# PMP20634_Sheet1.net
KiCad netlist of a schematic drawn in Altium Designer
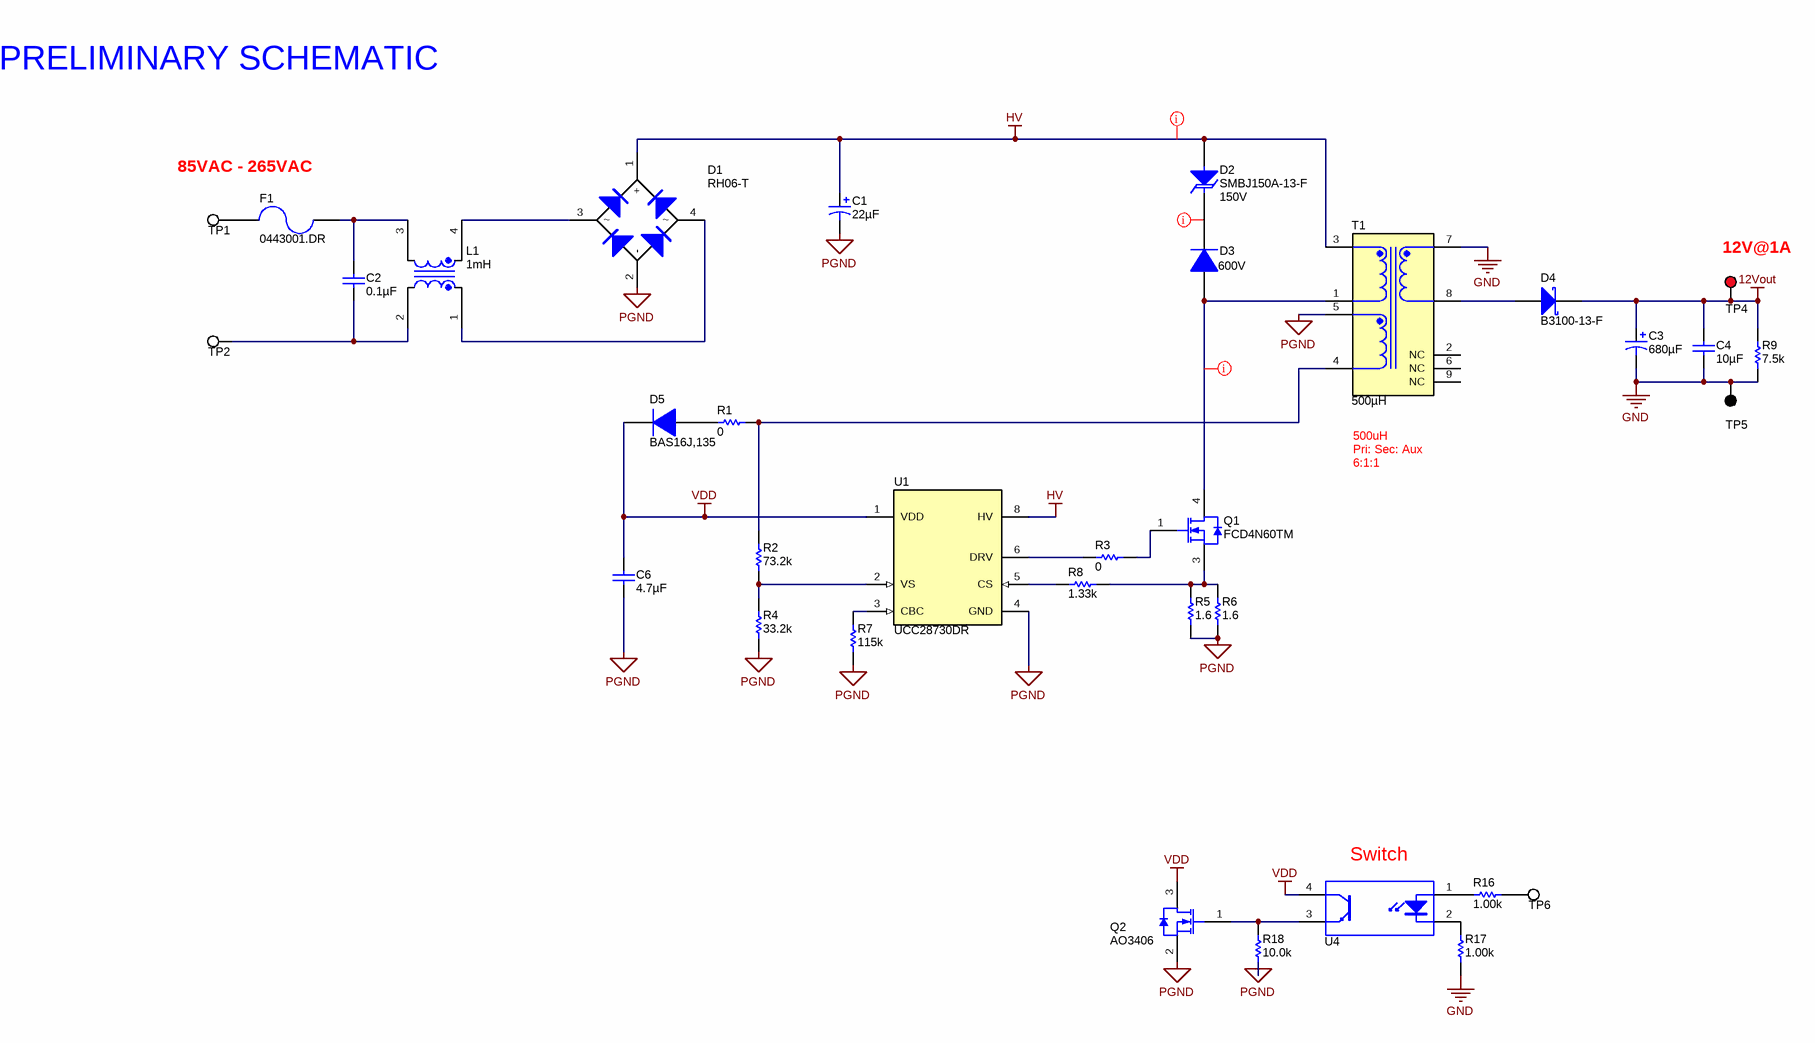
[diagram p0: PMP20634_Sheet1.SchDoc]

(export (version "E")
  (design (tool "Eeschema 10.0.6"))
  (components
    (comp (ref "C1")
      (value "EKXG401ELL220MK20S")
      (footprint "KXG_1250x2000")
      (description "CAP, AL, 22 µF, 400 V, +/- 20%, TH")
      (fields
        (field (name "VALUEDISPLAYED") "22µF")
        (field (name "MANUFACTURER") "Chemi-Con")
        (field (name "PUBLISHER") "Texas Instruments")
      )
      (libsource (lib "Capacitor_Aluminum") (part "EKXG401ELL220MK20S"))
    )
    (comp (ref "C2")
      (value "ECQ-U3A104MG")
      (footprint "ECQUG_1500x800x1500")
      (description "CAP, Film, 0.1 µF, 300 V, +/- 20%, TH")
      (fields
        (field (name "VALUEDISPLAYED") "0.1µF")
        (field (name "MANUFACTURER") "Panasonic")
        (field (name "PUBLISHER") "Texas Instruments")
      )
      (libsource (lib "Capacitor_Other") (part "ECQ-U3A104MG"))
    )
    (comp (ref "C3")
      (value "EKZE250ELL681MJ20S")
      (footprint "Chemi-Con_1000x2000")
      (description "CAP, AL, 680 µF, 25 V, +/- 20%, TH")
      (fields
        (field (name "VALUEDISPLAYED") "680µF")
        (field (name "MANUFACTURER") "Chemi-Con")
        (field (name "PUBLISHER") "Texas Instruments")
      )
      (libsource (lib "Capacitor_Aluminum") (part "EKZE250ELL681MJ20S"))
    )
    (comp (ref "C4")
      (value "GRM219R61E106KA12")
      (footprint "0805_HV")
      (description "CAP, CERM, 10 µF, 25 V, +/- 10%, X5R, 0805")
      (fields
        (field (name "VALUEDISPLAYED") "10µF")
        (field (name "MANUFACTURER") "MuRata")
        (field (name "PUBLISHER") "Texas Instruments")
      )
      (libsource (lib "Capacitor_Ceramic") (part "GRM219R61E106KA12"))
    )
    (comp (ref "C6")
      (value "GRM188R6YA475KE15D")
      (footprint "0603")
      (description "CAP, CERM, 4.7 µF, 35 V, +/- 10%, X5R, 0603")
      (fields
        (field (name "VALUEDISPLAYED") "4.7µF")
        (field (name "MANUFACTURER") "MuRata")
        (field (name "PUBLISHER") "Texas Instruments")
      )
      (libsource (lib "Capacitor_Ceramic") (part "GRM188R6YA475KE15D"))
    )
    (comp (ref "D1")
      (value "RH06-T")
      (footprint "MiniDIP")
      (description "Diode, Switching-Bridge, 600 V, 0.5 A, MiniDIP")
      (fields (field (name "MANUFACTURER") "Diodes Inc.") (field (name "PUBLISHER") "Texas Instruments"))
      (libsource (lib "Diode") (part "RH06-T"))
    )
    (comp (ref "D2")
      (value "SMBJ150A-13-F")
      (footprint "SMB")
      (description "Diode, TVS, Uni, 150 V, 243 Vc, SMB")
      (fields
        (field (name "ALTIUM_VALUE") "150V")
        (field (name "MANUFACTURER") "Diodes Inc.")
        (field (name "PUBLISHER") "Texas Instruments")
      )
      (libsource (lib "ZenerDiodes") (part "SMBJ150A-13-F"))
    )
    (comp (ref "D3")
      (value "MURA160T3G")
      (footprint "SMA")
      (description "Diode, Ultrafast, 600V, 1A, SMA")
      (fields
        (field (name "MANUFACTURER") "ON Semiconductor")
        (field (name "VALUE2") "600V")
        (field (name "PUBLISHER") "Texas Instruments")
      )
      (libsource (lib "Diode") (part "MURA160T3G"))
    )
    (comp (ref "D4")
      (value "B3100-13-F")
      (footprint "SMC")
      (description "Diode, Schottky, 100 V, 3 A, SMC")
      (fields (field (name "MANUFACTURER") "Diodes Inc.") (field (name "PUBLISHER") "Texas Instruments"))
      (libsource (lib "Diode") (part "B3100-13-F"))
    )
    (comp (ref "D5")
      (value "BAS16J,135")
      (footprint "SOD-323F")
      (description "Diode, Switching, 100 V, 0.25 A, SOD-323F")
      (fields
        (field (name "MANUFACTURER") "NXP Semiconductor")
        (field (name "PUBLISHER") "Texas Instruments")
      )
      (libsource (lib "Diode") (part "BAS16J,135"))
    )
    (comp (ref "F1")
      (value "0443001.DR")
      (footprint "FUSE_0443")
      (description "Fuse, 1 A, 250VAC/VDC, SMD")
      (fields (field (name "MANUFACTURER") "Littelfuse") (field (name "PUBLISHER") "Texas Instruments"))
      (libsource (lib "Fuse") (part "0443001.DR"))
    )
    (comp (ref "L1")
      (value "744821201")
      (footprint "WE-CMB_XS")
      (description "Coupled inductor, 1 mH, 2 A, 0.045 ohm, TH")
      (fields
        (field (name "VALUEDISPLAYED") "1mH")
        (field (name "MANUFACTURER") "Wurth Elektronik")
        (field (name "SYMBOLCREATOR") "a0412235")
        (field (name "PUBLISHER") "Texas Instruments")
      )
      (libsource (lib "Coupled_Inductors") (part "744821201"))
    )
    (comp (ref "Q1")
      (value "FCD4N60TM")
      (footprint "DPAK")
      (description "MOSFET, N-CH, 600 V, 3.9 A, DPAK")
      (fields
        (field (name "MANUFACTURER") "Fairchild Semiconductor")
        (field (name "PUBLISHER") "Texas Instruments")
      )
      (libsource (lib "FETs") (part "FCD4N60TM"))
    )
    (comp (ref "Q2")
      (value "AO3406")
      (footprint "SOT-23")
      (description "MOSFET, N-CH, 30 V, 3.6 A, SOT-23")
      (fields (field (name "MANUFACTURER") "AOS") (field (name "PUBLISHER") "Texas Instruments"))
      (libsource (lib "FETs") (part "AO3406"))
    )
    (comp (ref "R1")
      (value "CRCW04020000Z0ED")
      (footprint "0402")
      (description "RES, 0, 5%, 0.063 W, 0402")
      (fields
        (field (name "VALUEDISPLAYED") "0")
        (field (name "MANUFACTURER") "Vishay-Dale")
        (field (name "PUBLISHER") "Texas Instruments")
      )
      (libsource (lib "Resistor_0402") (part "CRCW04020000Z0ED"))
    )
    (comp (ref "R2")
      (value "CRCW040273K2FKED")
      (footprint "0402")
      (description "RES, 73.2 k, 1%, 0.063 W, 0402")
      (fields
        (field (name "VALUEDISPLAYED") "73.2k")
        (field (name "MANUFACTURER") "Vishay-Dale")
        (field (name "PUBLISHER") "Texas Instruments")
      )
      (libsource (lib "Resistor_0402") (part "CRCW040273K2FKED"))
    )
    (comp (ref "R3")
      (value "CRCW04020000Z0ED")
      (footprint "0402")
      (description "RES, 0, 5%, 0.063 W, 0402")
      (fields
        (field (name "VALUEDISPLAYED") "0")
        (field (name "MANUFACTURER") "Vishay-Dale")
        (field (name "PUBLISHER") "Texas Instruments")
      )
      (libsource (lib "Resistor_0402") (part "CRCW04020000Z0ED"))
    )
    (comp (ref "R4")
      (value "CRCW040233K2FKED")
      (footprint "0402")
      (description "RES, 33.2 k, 1%, 0.063 W, 0402")
      (fields
        (field (name "VALUEDISPLAYED") "33.2k")
        (field (name "MANUFACTURER") "Vishay-Dale")
        (field (name "PUBLISHER") "Texas Instruments")
      )
      (libsource (lib "Resistor_0402") (part "CRCW040233K2FKED"))
    )
    (comp (ref "R5")
      (value "CRCW08051R60JNEA")
      (footprint "0805_HV")
      (description "RES, 1.6, 5%, 0.125 W, 0805")
      (fields
        (field (name "VALUEDISPLAYED") "1.6")
        (field (name "MANUFACTURER") "Vishay-Dale")
        (field (name "PUBLISHER") "Texas Instruments")
      )
      (libsource (lib "Resistor_0805") (part "CRCW08051R60JNEA"))
    )
    (comp (ref "R6")
      (value "CRCW08051R60JNEA")
      (footprint "0805_HV")
      (description "RES, 1.6, 5%, 0.125 W, 0805")
      (fields
        (field (name "VALUEDISPLAYED") "1.6")
        (field (name "MANUFACTURER") "Vishay-Dale")
        (field (name "PUBLISHER") "Texas Instruments")
      )
      (libsource (lib "Resistor_0805") (part "CRCW08051R60JNEA"))
    )
    (comp (ref "R7")
      (value "CRCW0402115KFKED")
      (footprint "0402")
      (description "RES, 115 k, 1%, 0.063 W, 0402")
      (fields
        (field (name "VALUEDISPLAYED") "115k")
        (field (name "MANUFACTURER") "Vishay-Dale")
        (field (name "PUBLISHER") "Texas Instruments")
      )
      (libsource (lib "Resistor_0402") (part "CRCW0402115KFKED"))
    )
    (comp (ref "R8")
      (value "CRCW04021K33FKED")
      (footprint "0402")
      (description "RES, 1.33 k, 1%, 0.063 W, 0402")
      (fields
        (field (name "VALUEDISPLAYED") "1.33k")
        (field (name "MANUFACTURER") "Vishay-Dale")
        (field (name "PUBLISHER") "Texas Instruments")
      )
      (libsource (lib "Resistor_0402") (part "CRCW04021K33FKED"))
    )
    (comp (ref "R9")
      (value "CRCW04027K50JNED")
      (footprint "0402")
      (description "RES, 7.5 k, 5%, 0.063 W, 0402")
      (fields
        (field (name "VALUEDISPLAYED") "7.5k")
        (field (name "MANUFACTURER") "Vishay-Dale")
        (field (name "PUBLISHER") "Texas Instruments")
      )
      (libsource (lib "Resistor_0402") (part "CRCW04027K50JNED"))
    )
    (comp (ref "R16")
      (value "CRCW04021K00FKED")
      (footprint "0402")
      (description "RES, 1.00 k, 1%, 0.063 W, 0402")
      (fields
        (field (name "VALUEDISPLAYED") "1.00k")
        (field (name "MANUFACTURER") "Vishay-Dale")
        (field (name "PUBLISHER") "Texas Instruments")
      )
      (libsource (lib "Resistor_0402") (part "CRCW04021K00FKED"))
    )
    (comp (ref "R17")
      (value "CRCW04021K00FKED")
      (footprint "0402")
      (description "RES, 1.00 k, 1%, 0.063 W, 0402")
      (fields
        (field (name "VALUEDISPLAYED") "1.00k")
        (field (name "MANUFACTURER") "Vishay-Dale")
        (field (name "PUBLISHER") "Texas Instruments")
      )
      (libsource (lib "Resistor_0402") (part "CRCW04021K00FKED"))
    )
    (comp (ref "R18")
      (value "CRCW040210K0FKED")
      (footprint "0402")
      (description "RES, 10.0 k, 1%, 0.063 W, 0402")
      (fields
        (field (name "VALUEDISPLAYED") "10.0k")
        (field (name "MANUFACTURER") "Vishay-Dale")
        (field (name "PUBLISHER") "Texas Instruments")
      )
      (libsource (lib "Resistor_0402") (part "CRCW040210K0FKED"))
    )
    (comp (ref "T1")
      (value "750316686")
      (footprint "Wurth_EE16-8-5_5280")
      (description "Transformer, 500 uH, EE16/8/5, TH")
      (fields
        (field (name "VALUEDISPLAYED") "500µH")
        (field (name "MANUFACTURER") "Wurth Elektronik")
        (field (name "SYMBOLCREATOR") "a0411947")
        (field (name "PUBLISHER") "Texas Instruments")
      )
      (libsource (lib "Transformers") (part "750316686"))
    )
    (comp (ref "TP1")
      (value "5012")
      (footprint "Keystone5012")
      (description "Test Point, Multipurpose, White, TH")
      (fields (field (name "MANUFACTURER") "Keystone") (field (name "PUBLISHER") "Texas Instruments"))
      (libsource (lib "Connectors_Keystone") (part "5012"))
    )
    (comp (ref "TP2")
      (value "5012")
      (footprint "Keystone5012")
      (description "Test Point, Multipurpose, White, TH")
      (fields (field (name "MANUFACTURER") "Keystone") (field (name "PUBLISHER") "Texas Instruments"))
      (libsource (lib "Connectors_Keystone") (part "5012"))
    )
    (comp (ref "TP4")
      (value "5010")
      (footprint "Keystone5010")
      (description "Test Point, Multipurpose, Red, TH")
      (fields (field (name "MANUFACTURER") "Keystone") (field (name "PUBLISHER") "Texas Instruments"))
      (libsource (lib "Connectors_Keystone") (part "5010"))
    )
    (comp (ref "TP5")
      (value "5011")
      (footprint "Keystone5011")
      (description "Test Point, Multipurpose, Black, TH")
      (fields (field (name "MANUFACTURER") "Keystone") (field (name "PUBLISHER") "Texas Instruments"))
      (libsource (lib "Connectors_Keystone") (part "5011"))
    )
    (comp (ref "TP6")
      (value "5002")
      (footprint "Keystone5002")
      (description "Test Point, Miniature, White, TH")
      (fields (field (name "MANUFACTURER") "Keystone") (field (name "PUBLISHER") "Texas Instruments"))
      (libsource (lib "Connectors_Keystone") (part "5002"))
    )
    (comp (ref "U1")
      (value "UCC28730DR")
      (footprint "D0007A_N")
      (fields
        (field (name "ALTERNATE PARTNUMBER") "UCC28730D")
        (field (name "MANUFACTURER") "Texas Instruments")
        (field (name "SYMBOLCREATOR") "x0208325")
        (field (name "PUBLISHER") "Texas Instruments")
      )
      (libsource (lib "TI_Pre_Release1") (part "UCC28730DR"))
    )
    (comp (ref "U4")
      (value "VOS617A-7X001T")
      (footprint "SSOP-4_VISHAY")
      (description "Optocoupler, 3.75 kV, 80-160% CTR, SMT")
      (fields
        (field (name "MANUFACTURER") "Vishay-Semiconductor")
        (field (name "PUBLISHER") "Texas Instruments")
      )
      (libsource (lib "OptoCouplers") (part "VOS617A-7X001T"))
    )
  )
  (nets
    (net (code "1") (name "12Vout") (class "Default")
      (node (ref "C3") (pin "1") (pinfunction "+_1") (pintype "passive"))
      (node (ref "C4") (pin "1") (pinfunction "1_1") (pintype "passive"))
      (node (ref "D4") (pin "1") (pinfunction "K_1") (pintype "passive"))
      (node (ref "R9") (pin "2") (pinfunction "2_2") (pintype "passive"))
      (node (ref "TP4") (pin "1") (pintype "passive"))
    )
    (net (code "2") (name "GND") (class "Default")
      (node (ref "C3") (pin "2") (pinfunction "-_2") (pintype "passive"))
      (node (ref "C4") (pin "2") (pinfunction "2_2") (pintype "passive"))
      (node (ref "R17") (pin "2") (pinfunction "2_2") (pintype "passive"))
      (node (ref "R9") (pin "1") (pinfunction "1_1") (pintype "passive"))
      (node (ref "T1") (pin "7") (pinfunction "7_7") (pintype "passive"))
      (node (ref "TP5") (pin "1") (pintype "passive"))
    )
    (net (code "3") (name "HV") (class "Default")
      (node (ref "C1") (pin "1") (pinfunction "+_1") (pintype "passive"))
      (node (ref "D1") (pin "1") (pinfunction "+_1") (pintype "passive"))
      (node (ref "D2") (pin "2") (pinfunction "A_2") (pintype "passive"))
      (node (ref "T1") (pin "3") (pinfunction "3_3") (pintype "passive"))
      (node (ref "U1") (pin "8") (pinfunction "HV_8") (pintype "power_in"))
    )
    (net (code "4") (name "Net-(C2-Pad1)") (class "Default")
      (node (ref "C2") (pin "1") (pinfunction "1_1") (pintype "passive"))
      (node (ref "F1") (pin "1") (pinfunction "1_1") (pintype "passive"))
      (node (ref "L1") (pin "3") (pinfunction "3_3") (pintype "passive"))
    )
    (net (code "5") (name "Net-(C2-Pad2)") (class "Default")
      (node (ref "C2") (pin "2") (pinfunction "2_2") (pintype "passive"))
      (node (ref "L1") (pin "2") (pinfunction "2_2") (pintype "passive"))
      (node (ref "TP2") (pin "1") (pintype "passive"))
    )
    (net (code "6") (name "Net-(D1-~-Pad3)") (class "Default")
      (node (ref "D1") (pin "3") (pinfunction "~_3") (pintype "passive"))
      (node (ref "L1") (pin "4") (pinfunction "4_4") (pintype "passive"))
    )
    (net (code "7") (name "Net-(D1-~-Pad4)") (class "Default")
      (node (ref "D1") (pin "4") (pinfunction "~_4") (pintype "passive"))
      (node (ref "L1") (pin "1") (pinfunction "1_1") (pintype "passive"))
    )
    (net (code "8") (name "Net-(D2-K)") (class "Default")
      (node (ref "D2") (pin "1") (pinfunction "K_1") (pintype "passive"))
      (node (ref "D3") (pin "1") (pinfunction "K_1") (pintype "passive"))
    )
    (net (code "9") (name "Net-(D3-A)") (class "Default")
      (node (ref "D3") (pin "2") (pinfunction "A_2") (pintype "passive"))
      (node (ref "Q1") (pin "4") (pinfunction "D_4") (pintype "passive"))
      (node (ref "T1") (pin "1") (pinfunction "1_1") (pintype "passive"))
    )
    (net (code "10") (name "Net-(D4-A)") (class "Default")
      (node (ref "D4") (pin "2") (pinfunction "A_2") (pintype "passive"))
      (node (ref "T1") (pin "8") (pinfunction "8_8") (pintype "passive"))
    )
    (net (code "11") (name "Net-(D5-A)") (class "Default")
      (node (ref "D5") (pin "2") (pinfunction "A_2") (pintype "passive"))
      (node (ref "R1") (pin "1") (pinfunction "1_1") (pintype "passive"))
    )
    (net (code "12") (name "Net-(F1-Pad2)") (class "Default")
      (node (ref "F1") (pin "2") (pinfunction "2_2") (pintype "passive"))
      (node (ref "TP1") (pin "1") (pintype "passive"))
    )
    (net (code "13") (name "Net-(Q1-G)") (class "Default")
      (node (ref "Q1") (pin "1") (pinfunction "G_1") (pintype "passive"))
      (node (ref "R3") (pin "2") (pinfunction "2_2") (pintype "passive"))
    )
    (net (code "14") (name "Net-(Q1-S)") (class "Default")
      (node (ref "Q1") (pin "3") (pinfunction "S_3") (pintype "passive"))
      (node (ref "R5") (pin "2") (pinfunction "2_2") (pintype "passive"))
      (node (ref "R6") (pin "2") (pinfunction "2_2") (pintype "passive"))
      (node (ref "R8") (pin "2") (pinfunction "2_2") (pintype "passive"))
    )
    (net (code "15") (name "Net-(Q2-G)") (class "Default")
      (node (ref "Q2") (pin "1") (pinfunction "G_1") (pintype "passive"))
      (node (ref "R18") (pin "2") (pinfunction "2_2") (pintype "passive"))
      (node (ref "U4") (pin "3") (pinfunction "E_3") (pintype "passive"))
    )
    (net (code "16") (name "Net-(R1-Pad2)") (class "Default")
      (node (ref "R1") (pin "2") (pinfunction "2_2") (pintype "passive"))
      (node (ref "R2") (pin "2") (pinfunction "2_2") (pintype "passive"))
      (node (ref "T1") (pin "4") (pinfunction "4_4") (pintype "passive"))
    )
    (net (code "17") (name "Net-(R16-Pad1)") (class "Default")
      (node (ref "R16") (pin "1") (pinfunction "1_1") (pintype "passive"))
      (node (ref "TP6") (pin "1") (pintype "passive"))
    )
    (net (code "18") (name "Net-(U1-CBC)") (class "Default")
      (node (ref "R7") (pin "2") (pinfunction "2_2") (pintype "passive"))
      (node (ref "U1") (pin "3") (pinfunction "CBC_3") (pintype "input"))
    )
    (net (code "19") (name "Net-(U1-CS)") (class "Default")
      (node (ref "R8") (pin "1") (pinfunction "1_1") (pintype "passive"))
      (node (ref "U1") (pin "5") (pinfunction "CS_5") (pintype "input"))
    )
    (net (code "20") (name "Net-(U1-DRV)") (class "Default")
      (node (ref "R3") (pin "1") (pinfunction "1_1") (pintype "passive"))
      (node (ref "U1") (pin "6") (pinfunction "DRV_6") (pintype "power_in"))
    )
    (net (code "21") (name "Net-(U1-VS)") (class "Default")
      (node (ref "R2") (pin "1") (pinfunction "1_1") (pintype "passive"))
      (node (ref "R4") (pin "2") (pinfunction "2_2") (pintype "passive"))
      (node (ref "U1") (pin "2") (pinfunction "VS_2") (pintype "input"))
    )
    (net (code "22") (name "Net-(U4-A)") (class "Default")
      (node (ref "R16") (pin "2") (pinfunction "2_2") (pintype "passive"))
      (node (ref "U4") (pin "1") (pinfunction "A_1") (pintype "passive"))
    )
    (net (code "23") (name "Net-(U4-K)") (class "Default")
      (node (ref "R17") (pin "1") (pinfunction "1_1") (pintype "passive"))
      (node (ref "U4") (pin "2") (pinfunction "K_2") (pintype "passive"))
    )
    (net (code "24") (name "PGND") (class "Default")
      (node (ref "C1") (pin "2") (pinfunction "-_2") (pintype "passive"))
      (node (ref "C6") (pin "2") (pinfunction "2_2") (pintype "passive"))
      (node (ref "D1") (pin "2") (pinfunction "-_2") (pintype "passive"))
      (node (ref "Q2") (pin "2") (pinfunction "S_2") (pintype "passive"))
      (node (ref "R18") (pin "1") (pinfunction "1_1") (pintype "passive"))
      (node (ref "R4") (pin "1") (pinfunction "1_1") (pintype "passive"))
      (node (ref "R5") (pin "1") (pinfunction "1_1") (pintype "passive"))
      (node (ref "R6") (pin "1") (pinfunction "1_1") (pintype "passive"))
      (node (ref "R7") (pin "1") (pinfunction "1_1") (pintype "passive"))
      (node (ref "T1") (pin "5") (pinfunction "5_5") (pintype "passive"))
      (node (ref "U1") (pin "4") (pinfunction "GND_4") (pintype "power_in"))
    )
    (net (code "25") (name "VDD") (class "Default")
      (node (ref "C6") (pin "1") (pinfunction "1_1") (pintype "passive"))
      (node (ref "D5") (pin "1") (pinfunction "K_1") (pintype "passive"))
      (node (ref "Q2") (pin "3") (pinfunction "D_3") (pintype "passive"))
      (node (ref "U1") (pin "1") (pinfunction "VDD_1") (pintype "power_in"))
      (node (ref "U4") (pin "4") (pinfunction "C_4") (pintype "passive"))
    )
    (net (code "26") (name "unconnected-(T1-NC-Pad2)") (class "Default")
      (node (ref "T1") (pin "2") (pinfunction "NC_2") (pintype "passive"))
    )
    (net (code "27") (name "unconnected-(T1-NC-Pad6)") (class "Default")
      (node (ref "T1") (pin "6") (pinfunction "NC_6") (pintype "passive"))
    )
    (net (code "28") (name "unconnected-(T1-NC-Pad9)") (class "Default")
      (node (ref "T1") (pin "9") (pinfunction "NC_9") (pintype "passive"))
    )
  )
)
